# main.net
KiCad netlist of a schematic drawn in Altium Designer
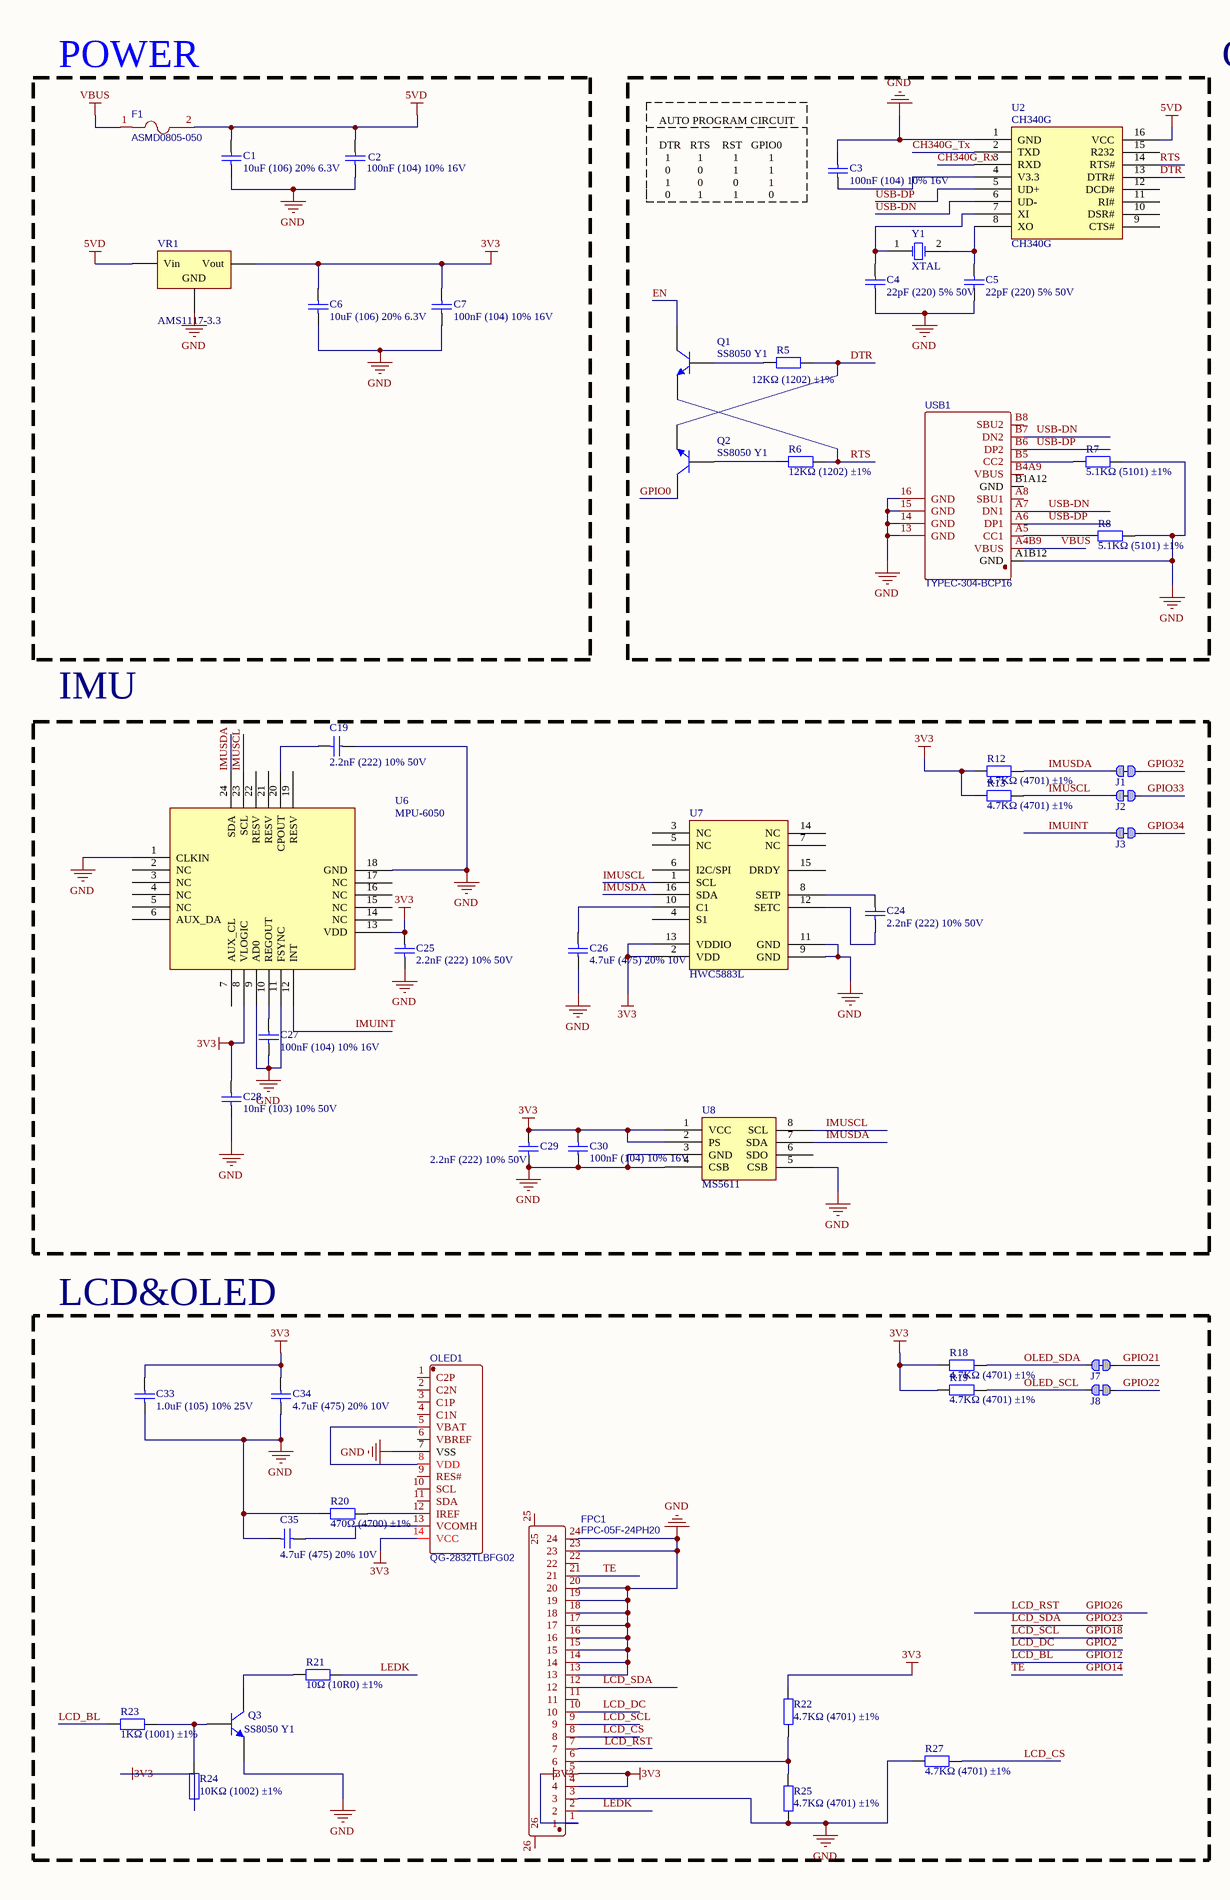
[diagram p0: main.SchDoc, left]
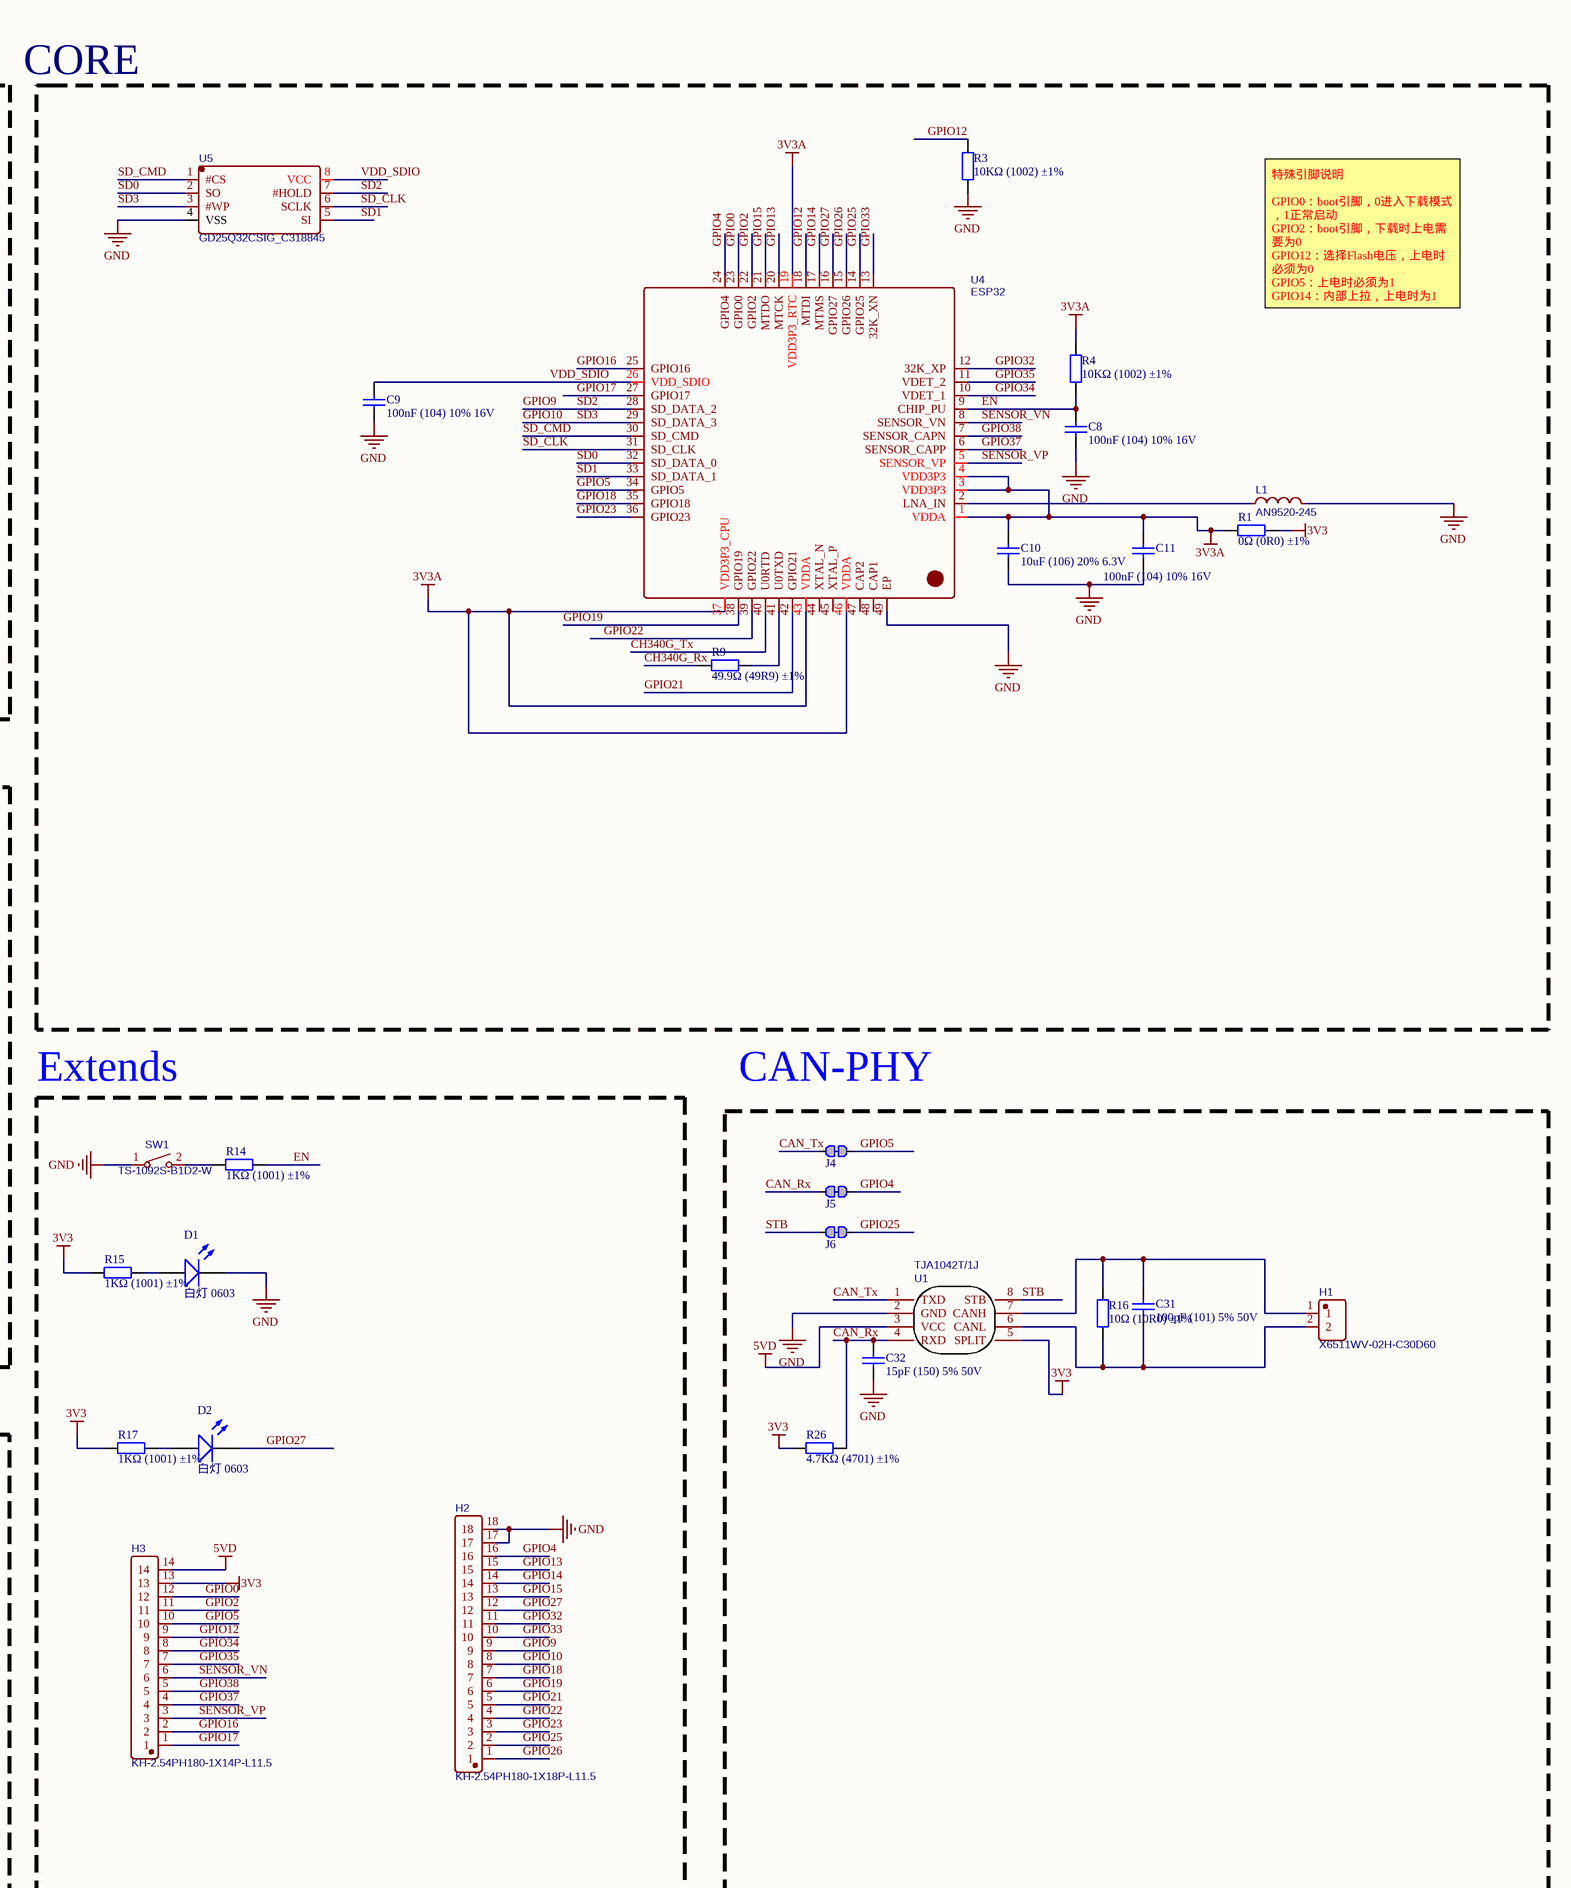
[diagram p1: main.SchDoc, right]

(export (version "E")
  (design (tool "Eeschema 10.0.6"))
  (components
    (comp (ref "C1")
      (value "10uF (106) 20% 6.3V")
      (footprint "0402_C")
      (description "贴片电容")
      (libsource (lib "Cap") (part "0402 10uF (106) 20% 6.3V"))
    )
    (comp (ref "C2")
      (value "100nF (104) 10% 16V")
      (footprint "0402_C")
      (description "贴片电容")
      (libsource (lib "Cap") (part "0402 100nF (104) 10% 16V"))
    )
    (comp (ref "C3")
      (value "100nF (104) 10% 16V")
      (footprint "0402_C")
      (description "贴片电容")
      (libsource (lib "Cap") (part "0402 100nF (104) 10% 16V"))
    )
    (comp (ref "C4")
      (value "22pF (220) 5% 50V")
      (footprint "0402_C")
      (description "贴片电容")
      (libsource (lib "Cap") (part "0402 22pF (220) 5% 50V"))
    )
    (comp (ref "C5")
      (value "22pF (220) 5% 50V")
      (footprint "0402_C")
      (description "贴片电容")
      (libsource (lib "Cap") (part "0402 22pF (220) 5% 50V"))
    )
    (comp (ref "C6")
      (value "10uF (106) 20% 6.3V")
      (footprint "0402_C")
      (description "贴片电容")
      (libsource (lib "Cap") (part "0402 10uF (106) 20% 6.3V"))
    )
    (comp (ref "C7")
      (value "100nF (104) 10% 16V")
      (footprint "0402_C")
      (description "贴片电容")
      (libsource (lib "Cap") (part "0402 100nF (104) 10% 16V"))
    )
    (comp (ref "C8")
      (value "100nF (104) 10% 16V")
      (footprint "0402_C")
      (description "贴片电容")
      (libsource (lib "Cap") (part "0402 100nF (104) 10% 16V"))
    )
    (comp (ref "C9")
      (value "100nF (104) 10% 16V")
      (footprint "0402_C")
      (description "贴片电容")
      (libsource (lib "Cap") (part "0402 100nF (104) 10% 16V"))
    )
    (comp (ref "C10")
      (value "10uF (106) 20% 6.3V")
      (footprint "0402_C")
      (description "贴片电容")
      (libsource (lib "Cap") (part "0402 10uF (106) 20% 6.3V"))
    )
    (comp (ref "C11")
      (value "100nF (104) 10% 16V")
      (footprint "0402_C")
      (description "贴片电容")
      (libsource (lib "Cap") (part "0402 100nF (104) 10% 16V"))
    )
    (comp (ref "C19")
      (value "2.2nF (222) 10% 50V")
      (footprint "0402_C")
      (description "贴片电容")
      (libsource (lib "Cap") (part "0402 2.2nF (222) 10% 50V"))
    )
    (comp (ref "C24")
      (value "2.2nF (222) 10% 50V")
      (footprint "0603_C")
      (description "贴片电容")
      (libsource (lib "Cap") (part "0603 2.2nF (222) 10% 50V"))
    )
    (comp (ref "C25")
      (value "2.2nF (222) 10% 50V")
      (footprint "0402_C")
      (description "贴片电容")
      (libsource (lib "Cap") (part "0402 2.2nF (222) 10% 50V"))
    )
    (comp (ref "C26")
      (value "4.7uF (475) 20% 10V")
      (footprint "0402_C")
      (description "贴片电容")
      (libsource (lib "Cap") (part "0402 4.7uF (475) 20% 10V"))
    )
    (comp (ref "C27")
      (value "100nF (104) 10% 16V")
      (footprint "0402_C")
      (description "贴片电容")
      (libsource (lib "Cap") (part "0402 100nF (104) 10% 16V"))
    )
    (comp (ref "C28")
      (value "10nF (103) 10% 50V")
      (footprint "0402_C")
      (description "贴片电容")
      (libsource (lib "Cap") (part "0402 10nF (103) 10% 50V"))
    )
    (comp (ref "C29")
      (value "2.2nF (222) 10% 50V")
      (footprint "0402_C")
      (description "贴片电容")
      (libsource (lib "Cap") (part "0402 2.2nF (222) 10% 50V"))
    )
    (comp (ref "C30")
      (value "100nF (104) 10% 16V")
      (footprint "0402_C")
      (description "贴片电容")
      (libsource (lib "Cap") (part "0402 100nF (104) 10% 16V"))
    )
    (comp (ref "C31")
      (value "100pF (101) 5% 50V")
      (footprint "0402_C")
      (description "贴片电容")
      (libsource (lib "Cap") (part "0402 100pF (101) 5% 50V"))
    )
    (comp (ref "C32")
      (value "15pF (150) 5% 50V")
      (footprint "0402_C")
      (description "贴片电容")
      (libsource (lib "Cap") (part "0402 15pF (150) 5% 50V"))
    )
    (comp (ref "C33")
      (value "1.0uF (105) 10% 25V")
      (footprint "0402_C")
      (description "贴片电容")
      (libsource (lib "Cap") (part "0402 1.0uF (105) 10% 25V"))
    )
    (comp (ref "C34")
      (value "4.7uF (475) 20% 10V")
      (footprint "0402_C")
      (description "贴片电容")
      (libsource (lib "Cap") (part "0402 4.7uF (475) 20% 10V"))
    )
    (comp (ref "C35")
      (value "4.7uF (475) 20% 10V")
      (footprint "0402_C")
      (description "贴片电容")
      (libsource (lib "Cap") (part "0402 4.7uF (475) 20% 10V"))
    )
    (comp (ref "D1")
      (value "白灯 0603")
      (footprint "0603_LED_S1")
      (description "发光二极管")
      (libsource (lib "Miscellaneous Devices LC") (part "0603 白灯"))
    )
    (comp (ref "D2")
      (value "白灯 0603")
      (footprint "0603_LED_S1")
      (description "发光二极管")
      (libsource (lib "Miscellaneous Devices LC") (part "0603 白灯"))
    )
    (comp (ref "F1")
      (value "ASMD0805-050")
      (footprint "F0805")
      (fields (field (name "BOM_SUPPLIER PART") "C135329"))
      (libsource (lib "mypkg") (part "ASMD0805-050"))
    )
    (comp (ref "FPC1")
      (value "FPC-05F-24PH20")
      (footprint "FPC-SMD_24P-P0.50_FPC-05F-24PH20")
      (description "FPC24脚")
      (fields (field (name "BOM_SUPPLIER PART") "C2856805"))
      (libsource (lib "mysch") (part "FPC-05F-24PH20"))
    )
    (comp (ref "H1")
      (value "X6511WV-02H-C30D60")
      (footprint "HDR-TH_2P-P2.54-V-M")
      (fields (field (name "BOM_SUPPLIER PART") "C706874"))
      (libsource (lib "mysch") (part "HDR-2P"))
    )
    (comp (ref "H2")
      (value "KH-2.54PH180-1X18P-L11.5")
      (footprint "HDR-TH_18P-P2.54-V-M")
      (fields (field (name "BOM_SUPPLIER PART") "C2905492"))
      (libsource (lib "mysch") (part "HDR-18P"))
    )
    (comp (ref "H3")
      (value "KH-2.54PH180-1X14P-L11.5")
      (footprint "HDR-TH_14P-P2.54-V-M")
      (description "排针")
      (fields (field (name "BOM_SUPPLIER PART") "C2905490"))
      (libsource (lib "mysch") (part "HDR-14P"))
    )
    (comp (ref "J1")
      (value "跳线")
      (footprint "RES_0402")
      (description "Resistor")
      (libsource (lib "mysch") (part "跳线"))
    )
    (comp (ref "J2")
      (value "跳线")
      (footprint "RES_0402")
      (description "Resistor")
      (libsource (lib "mysch") (part "跳线"))
    )
    (comp (ref "J3")
      (value "跳线")
      (footprint "RES_0402")
      (description "Resistor")
      (libsource (lib "mysch") (part "跳线"))
    )
    (comp (ref "J4")
      (value "跳线")
      (footprint "RES_0402")
      (description "Resistor")
      (libsource (lib "mysch") (part "跳线"))
    )
    (comp (ref "J5")
      (value "跳线")
      (footprint "RES_0402")
      (description "Resistor")
      (libsource (lib "mysch") (part "跳线"))
    )
    (comp (ref "J6")
      (value "跳线")
      (footprint "RES_0402")
      (description "Resistor")
      (libsource (lib "mysch") (part "跳线"))
    )
    (comp (ref "J7")
      (value "跳线")
      (footprint "RES_0402")
      (description "Resistor")
      (libsource (lib "mysch") (part "跳线"))
    )
    (comp (ref "J8")
      (value "跳线")
      (footprint "RES_0402")
      (description "Resistor")
      (libsource (lib "mysch") (part "跳线"))
    )
    (comp (ref "L1")
      (value "AN9520-245")
      (footprint "ANT-SMD_L9.5-W2.1")
      (description "陶瓷wifi/bt天线")
      (fields (field (name "BOM_SUPPLIER PART") "C99665"))
      (libsource (lib "mypkg") (part "AN9520-245"))
    )
    (comp (ref "OLED1")
      (value "QG-2832TLBFG02")
      (footprint "OLED-SMD_QG-9616TSWCG02")
      (fields (field (name "BOM_SUPPLIER PART") "C91220"))
      (libsource (lib "mysch") (part "OLED"))
    )
    (comp (ref "Q1")
      (value "SS8050 Y1")
      (footprint "SOT-23(SOT-23-3)")
      (description "三极管")
      (libsource (lib "Miscellaneous Devices LC") (part "SOT-23 SS8050 Y1"))
    )
    (comp (ref "Q2")
      (value "SS8050 Y1")
      (footprint "SOT-23(SOT-23-3)")
      (description "三极管")
      (libsource (lib "Miscellaneous Devices LC") (part "SOT-23 SS8050 Y1"))
    )
    (comp (ref "Q3")
      (value "SS8050 Y1")
      (footprint "SOT-23(SOT-23-3)")
      (description "三极管")
      (libsource (lib "Miscellaneous Devices LC") (part "SOT-23 SS8050 Y1"))
    )
    (comp (ref "R1")
      (value "0Ω (0R0) ±1%")
      (footprint "0402_R")
      (description "贴片电阻")
      (libsource (lib "RES") (part "0402 0Ω (0R0) 1%"))
    )
    (comp (ref "R3")
      (value "10KΩ (1002) ±1%")
      (footprint "0402_R")
      (description "贴片电阻")
      (libsource (lib "RES") (part "0402 10KΩ (1002) 1%"))
    )
    (comp (ref "R4")
      (value "10KΩ (1002) ±1%")
      (footprint "0402_R")
      (description "贴片电阻")
      (libsource (lib "RES") (part "0402 10KΩ (1002) 1%"))
    )
    (comp (ref "R5")
      (value "12KΩ (1202) ±1%")
      (footprint "0402_R")
      (description "贴片电阻")
      (libsource (lib "RES") (part "0402 12KΩ (1202) 1%"))
    )
    (comp (ref "R6")
      (value "12KΩ (1202) ±1%")
      (footprint "0402_R")
      (description "贴片电阻")
      (libsource (lib "RES") (part "0402 12KΩ (1202) 1%"))
    )
    (comp (ref "R7")
      (value "5.1KΩ (5101) ±1%")
      (footprint "0402_R")
      (description "贴片电阻")
      (libsource (lib "RES") (part "0402 5.1KΩ (5101) 1%"))
    )
    (comp (ref "R8")
      (value "5.1KΩ (5101) ±1%")
      (footprint "0402_R")
      (description "贴片电阻")
      (libsource (lib "RES") (part "0402 5.1KΩ (5101) 1%"))
    )
    (comp (ref "R9")
      (value "49.9Ω (49R9) ±1%")
      (footprint "0402_R")
      (description "贴片电阻")
      (libsource (lib "RES") (part "0402 49.9Ω (49R9) 1%"))
    )
    (comp (ref "R12")
      (value "4.7KΩ (4701) ±1%")
      (footprint "0402_R")
      (description "贴片电阻")
      (libsource (lib "") (part "0402 4.7KΩ (4701) 1%_1"))
    )
    (comp (ref "R13")
      (value "4.7KΩ (4701) ±1%")
      (footprint "0402_R")
      (description "贴片电阻")
      (libsource (lib "") (part "0402 4.7KΩ (4701) 1%_1"))
    )
    (comp (ref "R14")
      (value "1KΩ (1001) ±1%")
      (footprint "0402_R")
      (description "贴片电阻")
      (libsource (lib "RES") (part "0402 1KΩ (1001) 1%"))
    )
    (comp (ref "R15")
      (value "1KΩ (1001) ±1%")
      (footprint "0402_R")
      (description "贴片电阻")
      (libsource (lib "RES") (part "0402 1KΩ (1001) 1%"))
    )
    (comp (ref "R16")
      (value "10Ω (10R0) ±1%")
      (footprint "0402_R")
      (description "贴片电阻")
      (libsource (lib "") (part "0402 10Ω (10R0) 1%_1"))
    )
    (comp (ref "R17")
      (value "1KΩ (1001) ±1%")
      (footprint "0402_R")
      (description "贴片电阻")
      (libsource (lib "RES") (part "0402 1KΩ (1001) 1%"))
    )
    (comp (ref "R18")
      (value "4.7KΩ (4701) ±1%")
      (footprint "0402_R")
      (description "贴片电阻")
      (libsource (lib "") (part "0402 4.7KΩ (4701) 1%_1"))
    )
    (comp (ref "R19")
      (value "4.7KΩ (4701) ±1%")
      (footprint "0402_R")
      (description "贴片电阻")
      (libsource (lib "") (part "0402 4.7KΩ (4701) 1%_1"))
    )
    (comp (ref "R20")
      (value "470Ω (4700) ±1%")
      (footprint "0402_R")
      (description "贴片电阻")
      (libsource (lib "RES") (part "0402 470Ω (4700) 1%"))
    )
    (comp (ref "R21")
      (value "10Ω (10R0) ±1%")
      (footprint "0402_R")
      (description "贴片电阻")
      (libsource (lib "RES") (part "0402 10Ω (10R0) 1%"))
    )
    (comp (ref "R22")
      (value "4.7KΩ (4701) ±1%")
      (footprint "0402_R")
      (description "贴片电阻")
      (libsource (lib "RES") (part "0402 4.7KΩ (4701) 1%"))
    )
    (comp (ref "R23")
      (value "1KΩ (1001) ±1%")
      (footprint "0402_R")
      (description "贴片电阻")
      (libsource (lib "RES") (part "0402 1KΩ (1001) 1%"))
    )
    (comp (ref "R24")
      (value "10KΩ (1002) ±1%")
      (footprint "0402_R")
      (description "贴片电阻")
      (libsource (lib "RES") (part "0402 10KΩ (1002) 1%"))
    )
    (comp (ref "R25")
      (value "4.7KΩ (4701) ±1%")
      (footprint "0402_R")
      (description "贴片电阻")
      (libsource (lib "RES") (part "0402 4.7KΩ (4701) 1%"))
    )
    (comp (ref "R26")
      (value "4.7KΩ (4701) ±1%")
      (footprint "0402_R")
      (description "贴片电阻")
      (libsource (lib "") (part "0402 4.7KΩ (4701) 1%_1"))
    )
    (comp (ref "R27")
      (value "4.7KΩ (4701) ±1%")
      (footprint "0402_R")
      (description "贴片电阻")
      (libsource (lib "") (part "0402 4.7KΩ (4701) 1%_1"))
    )
    (comp (ref "SW1")
      (value "TS-1092S-B1D2-W")
      (footprint "SW-SMD_L6.1-W3.6-LS7.9")
      (description "触控开关")
      (fields (field (name "BOM_SUPPLIER PART") "C782859"))
      (libsource (lib "mysch") (part "TS-1092S-B1D2-W"))
    )
    (comp (ref "U1")
      (value "TJA1042T/1J")
      (footprint "SOIC-8_L5.0-W4.0-P1.27-LS6.0-BL")
      (description "CAN芯片")
      (fields (field (name "BOM_SUPPLIER PART") "C53670"))
      (libsource (lib "mysch") (part "TJA1042T/1J"))
    )
    (comp (ref "U2")
      (value "CH340G")
      (footprint "SOIC-16_150mil")
      (description "USB")
      (libsource (lib "IC") (part "CH340G_[C14267]"))
    )
    (comp (ref "U4")
      (value "ESP32")
      (footprint "QFN-48-EP3.8")
      (fields (field (name "BOM_SUPPLIER PART") "C80134"))
      (libsource (lib "mypkg") (part "ESP32"))
    )
    (comp (ref "U5")
      (value "GD25Q32CSIG_C318845")
      (footprint "SOIC-8_L5.3-W5.3-P1.27-LS8.0-BL")
      (fields
        (field (name "BOM_SUPPLIER PART") "C318845")
        (field (name "BOM_MANUFACTURER PART") "GD25Q32CSIG")
      )
      (libsource (lib "mysch") (part "GD25Q32CSIG_C318845"))
    )
    (comp (ref "U6")
      (value "MPU-6050")
      (footprint "QFN-24_4x4x05P")
      (description "传感器")
      (libsource (lib "IC") (part "MPU-6050_[C24112]"))
    )
    (comp (ref "U7")
      (value "HWC5883L")
      (footprint "LPCC-16_L3.0-W3.0-P0.50-BL")
      (libsource (lib "mypkg") (part "HMC5883L"))
    )
    (comp (ref "U8") (value "MS5611") (footprint "MS5611") (libsource (lib "mysch") (part "MS5611")))
    (comp (ref "USB1")
      (value "TYPEC-304-BCP16")
      (footprint "USB-C-SMD_TYPEC-304-BCP16")
      (fields (field (name "BOM_SUPPLIER PART") "C720629"))
      (libsource (lib "mysch") (part "TYPEC-304-BCP16"))
    )
    (comp (ref "VR1")
      (value "AMS1117-3.3")
      (footprint "SOT-223")
      (description "低压差线性稳压(LDO)")
      (libsource (lib "LDO") (part "SOT-223 AMS1117-3.3"))
    )
    (comp (ref "Y1")
      (value "XTAL")
      (footprint "XTAL_socket")
      (description "Crystal Oscillator")
      (libsource (lib "mysch") (part "XTAL"))
    )
  )
  (nets
    (net (code "1") (name "/CAN_Rx") (class "Default")
      (node (ref "C32") (pin "2") (pinfunction "2_2") (pintype "passive"))
      (node (ref "J5") (pin "1") (pinfunction "1_1") (pintype "passive"))
      (node (ref "R26") (pin "2") (pinfunction "2_2") (pintype "passive"))
      (node (ref "U1") (pin "4") (pinfunction "RXD_4") (pintype "passive"))
    )
    (net (code "2") (name "/CAN_Tx") (class "Default")
      (node (ref "J4") (pin "1") (pinfunction "1_1") (pintype "passive"))
      (node (ref "U1") (pin "1") (pinfunction "TXD_1") (pintype "passive"))
    )
    (net (code "3") (name "/CH340G_Rx") (class "Default")
      (node (ref "R9") (pin "1") (pinfunction "1_1") (pintype "passive"))
      (node (ref "U2") (pin "3") (pinfunction "RXD_3") (pintype "passive"))
    )
    (net (code "4") (name "/CH340G_Tx") (class "Default")
      (node (ref "U2") (pin "2") (pinfunction "TXD_2") (pintype "passive"))
      (node (ref "U4") (pin "40") (pinfunction "U0RTD_40") (pintype "passive"))
    )
    (net (code "5") (name "/DTR") (class "Default")
      (node (ref "Q2") (pin "2") (pinfunction "E_2") (pintype "passive"))
      (node (ref "R5") (pin "2") (pinfunction "2_2") (pintype "passive"))
      (node (ref "U2") (pin "13") (pinfunction "DTR#_13") (pintype "passive"))
    )
    (net (code "6") (name "/EN") (class "Default")
      (node (ref "C8") (pin "2") (pinfunction "2_2") (pintype "passive"))
      (node (ref "Q1") (pin "3") (pinfunction "C_3") (pintype "passive"))
      (node (ref "R14") (pin "2") (pinfunction "2_2") (pintype "passive"))
      (node (ref "R4") (pin "1") (pinfunction "1_1") (pintype "passive"))
      (node (ref "U4") (pin "9") (pinfunction "CHIP_PU_9") (pintype "passive"))
    )
    (net (code "7") (name "/GPIO0") (class "Default")
      (node (ref "H3") (pin "12") (pinfunction "12_12") (pintype "passive"))
      (node (ref "Q2") (pin "3") (pinfunction "C_3") (pintype "passive"))
      (node (ref "U4") (pin "23") (pinfunction "GPIO0_23") (pintype "passive"))
    )
    (net (code "8") (name "/GPIO2") (class "Default")
      (node (ref "FPC1") (pin "10") (pinfunction "10_10") (pintype "passive"))
      (node (ref "H3") (pin "11") (pinfunction "11_11") (pintype "passive"))
      (node (ref "U4") (pin "22") (pinfunction "GPIO2_22") (pintype "passive"))
    )
    (net (code "9") (name "/GPIO4") (class "Default")
      (node (ref "H2") (pin "16") (pinfunction "16_16") (pintype "passive"))
      (node (ref "J5") (pin "2") (pinfunction "2_2") (pintype "passive"))
      (node (ref "U4") (pin "24") (pinfunction "GPIO4_24") (pintype "passive"))
    )
    (net (code "10") (name "/GPIO5") (class "Default")
      (node (ref "H3") (pin "10") (pinfunction "10_10") (pintype "passive"))
      (node (ref "J4") (pin "2") (pinfunction "2_2") (pintype "passive"))
      (node (ref "U4") (pin "34") (pinfunction "GPIO5_34") (pintype "passive"))
    )
    (net (code "11") (name "/GPIO9") (class "Default")
      (node (ref "H2") (pin "9") (pinfunction "9_9") (pintype "passive"))
      (node (ref "U4") (pin "28") (pinfunction "SD_DATA_2_28") (pintype "passive"))
      (node (ref "U5") (pin "7") (pinfunction "#HOLD_7") (pintype "passive"))
    )
    (net (code "12") (name "/GPIO10") (class "Default")
      (node (ref "H2") (pin "8") (pinfunction "8_8") (pintype "passive"))
      (node (ref "U4") (pin "29") (pinfunction "SD_DATA_3_29") (pintype "passive"))
      (node (ref "U5") (pin "3") (pinfunction "#WP_3") (pintype "passive"))
    )
    (net (code "13") (name "/GPIO12") (class "Default")
      (node (ref "H3") (pin "9") (pinfunction "9_9") (pintype "passive"))
      (node (ref "R23") (pin "1") (pinfunction "1_1") (pintype "passive"))
      (node (ref "R3") (pin "2") (pinfunction "2_2") (pintype "passive"))
      (node (ref "U4") (pin "18") (pinfunction "MTDI_18") (pintype "passive"))
    )
    (net (code "14") (name "/GPIO13") (class "Default")
      (node (ref "H2") (pin "15") (pinfunction "15_15") (pintype "passive"))
      (node (ref "U4") (pin "20") (pinfunction "MTCK_20") (pintype "passive"))
    )
    (net (code "15") (name "/GPIO14") (class "Default")
      (node (ref "FPC1") (pin "21") (pinfunction "21_21") (pintype "passive"))
      (node (ref "H2") (pin "14") (pinfunction "14_14") (pintype "passive"))
      (node (ref "U4") (pin "17") (pinfunction "MTMS_17") (pintype "passive"))
    )
    (net (code "16") (name "/GPIO15") (class "Default")
      (node (ref "H2") (pin "13") (pinfunction "13_13") (pintype "passive"))
      (node (ref "U4") (pin "21") (pinfunction "MTDO_21") (pintype "passive"))
    )
    (net (code "17") (name "/GPIO16") (class "Default")
      (node (ref "H3") (pin "2") (pinfunction "2_2") (pintype "passive"))
      (node (ref "U4") (pin "25") (pinfunction "GPIO16_25") (pintype "passive"))
    )
    (net (code "18") (name "/GPIO17") (class "Default")
      (node (ref "H3") (pin "1") (pinfunction "1_1") (pintype "passive"))
      (node (ref "U4") (pin "27") (pinfunction "GPIO17_27") (pintype "passive"))
    )
    (net (code "19") (name "/GPIO18") (class "Default")
      (node (ref "FPC1") (pin "9") (pinfunction "9_9") (pintype "passive"))
      (node (ref "H2") (pin "7") (pinfunction "7_7") (pintype "passive"))
      (node (ref "U4") (pin "35") (pinfunction "GPIO18_35") (pintype "passive"))
    )
    (net (code "20") (name "/GPIO19") (class "Default")
      (node (ref "H2") (pin "6") (pinfunction "6_6") (pintype "passive"))
      (node (ref "U4") (pin "38") (pinfunction "GPIO19_38") (pintype "passive"))
    )
    (net (code "21") (name "/GPIO21") (class "Default")
      (node (ref "H2") (pin "5") (pinfunction "5_5") (pintype "passive"))
      (node (ref "J7") (pin "2") (pinfunction "2_2") (pintype "passive"))
      (node (ref "U4") (pin "42") (pinfunction "GPIO21_42") (pintype "passive"))
    )
    (net (code "22") (name "/GPIO22") (class "Default")
      (node (ref "H2") (pin "4") (pinfunction "4_4") (pintype "passive"))
      (node (ref "J8") (pin "2") (pinfunction "2_2") (pintype "passive"))
      (node (ref "U4") (pin "39") (pinfunction "GPIO22_39") (pintype "passive"))
    )
    (net (code "23") (name "/GPIO23") (class "Default")
      (node (ref "FPC1") (pin "12") (pinfunction "12_12") (pintype "passive"))
      (node (ref "H2") (pin "3") (pinfunction "3_3") (pintype "passive"))
      (node (ref "U4") (pin "36") (pinfunction "GPIO23_36") (pintype "passive"))
    )
    (net (code "24") (name "/GPIO25") (class "Default")
      (node (ref "H2") (pin "2") (pinfunction "2_2") (pintype "passive"))
      (node (ref "J6") (pin "2") (pinfunction "2_2") (pintype "passive"))
      (node (ref "U4") (pin "14") (pinfunction "GPIO25_14") (pintype "passive"))
    )
    (net (code "25") (name "/GPIO26") (class "Default")
      (node (ref "FPC1") (pin "7") (pinfunction "7_7") (pintype "passive"))
      (node (ref "H2") (pin "1") (pinfunction "1_1") (pintype "passive"))
      (node (ref "U4") (pin "15") (pinfunction "GPIO26_15") (pintype "passive"))
    )
    (net (code "26") (name "/GPIO27") (class "Default")
      (node (ref "D2") (pin "K") (pinfunction "K_K") (pintype "passive"))
      (node (ref "H2") (pin "12") (pinfunction "12_12") (pintype "passive"))
      (node (ref "U4") (pin "16") (pinfunction "GPIO27_16") (pintype "passive"))
    )
    (net (code "27") (name "/GPIO32") (class "Default")
      (node (ref "H2") (pin "11") (pinfunction "11_11") (pintype "passive"))
      (node (ref "J1") (pin "2") (pinfunction "2_2") (pintype "passive"))
      (node (ref "U4") (pin "12") (pinfunction "32K_XP_12") (pintype "passive"))
    )
    (net (code "28") (name "/GPIO33") (class "Default")
      (node (ref "H2") (pin "10") (pinfunction "10_10") (pintype "passive"))
      (node (ref "J2") (pin "2") (pinfunction "2_2") (pintype "passive"))
      (node (ref "U4") (pin "13") (pinfunction "32K_XN_13") (pintype "passive"))
    )
    (net (code "29") (name "/GPIO34") (class "Default")
      (node (ref "H3") (pin "8") (pinfunction "8_8") (pintype "passive"))
      (node (ref "J3") (pin "2") (pinfunction "2_2") (pintype "passive"))
      (node (ref "U4") (pin "10") (pinfunction "VDET_1_10") (pintype "passive"))
    )
    (net (code "30") (name "/GPIO35") (class "Default")
      (node (ref "H3") (pin "7") (pinfunction "7_7") (pintype "passive"))
      (node (ref "U4") (pin "11") (pinfunction "VDET_2_11") (pintype "passive"))
    )
    (net (code "31") (name "/GPIO37") (class "Default")
      (node (ref "H3") (pin "4") (pinfunction "4_4") (pintype "passive"))
      (node (ref "U4") (pin "6") (pinfunction "SENSOR_CAPP_6") (pintype "passive"))
    )
    (net (code "32") (name "/GPIO38") (class "Default")
      (node (ref "H3") (pin "5") (pinfunction "5_5") (pintype "passive"))
      (node (ref "U4") (pin "7") (pinfunction "SENSOR_CAPN_7") (pintype "passive"))
    )
    (net (code "33") (name "/IMUINT") (class "Default")
      (node (ref "J3") (pin "1") (pinfunction "1_1") (pintype "passive"))
      (node (ref "U6") (pin "12") (pinfunction "INT_12") (pintype "passive"))
    )
    (net (code "34") (name "/IMUSCL") (class "Default")
      (node (ref "J2") (pin "1") (pinfunction "1_1") (pintype "passive"))
      (node (ref "R13") (pin "2") (pinfunction "2_2") (pintype "passive"))
      (node (ref "U6") (pin "23") (pinfunction "SCL_23") (pintype "passive"))
      (node (ref "U7") (pin "1") (pinfunction "SCL_1") (pintype "passive"))
      (node (ref "U8") (pin "8") (pinfunction "SCL_8") (pintype "passive"))
    )
    (net (code "35") (name "/IMUSDA") (class "Default")
      (node (ref "J1") (pin "1") (pinfunction "1_1") (pintype "passive"))
      (node (ref "R12") (pin "2") (pinfunction "2_2") (pintype "passive"))
      (node (ref "U6") (pin "24") (pinfunction "SDA_24") (pintype "passive"))
      (node (ref "U7") (pin "16") (pinfunction "SDA_16") (pintype "passive"))
      (node (ref "U8") (pin "7") (pinfunction "SDA_7") (pintype "passive"))
    )
    (net (code "36") (name "/LCD_CS") (class "Default")
      (node (ref "FPC1") (pin "8") (pinfunction "8_8") (pintype "passive"))
      (node (ref "R27") (pin "2") (pinfunction "2_2") (pintype "passive"))
    )
    (net (code "37") (name "/LEDK") (class "Default")
      (node (ref "FPC1") (pin "2") (pinfunction "2_2") (pintype "passive"))
      (node (ref "R21") (pin "2") (pinfunction "2_2") (pintype "passive"))
    )
    (net (code "38") (name "/OLED_SCL") (class "Default")
      (node (ref "J8") (pin "1") (pinfunction "1_1") (pintype "passive"))
      (node (ref "R19") (pin "2") (pinfunction "2_2") (pintype "passive"))
    )
    (net (code "39") (name "/OLED_SDA") (class "Default")
      (node (ref "J7") (pin "1") (pinfunction "1_1") (pintype "passive"))
      (node (ref "R18") (pin "2") (pinfunction "2_2") (pintype "passive"))
    )
    (net (code "40") (name "/RTS") (class "Default")
      (node (ref "Q1") (pin "2") (pinfunction "E_2") (pintype "passive"))
      (node (ref "R6") (pin "2") (pinfunction "2_2") (pintype "passive"))
      (node (ref "U2") (pin "14") (pinfunction "RTS#_14") (pintype "passive"))
    )
    (net (code "41") (name "/SD0") (class "Default")
      (node (ref "U4") (pin "32") (pinfunction "SD_DATA_0_32") (pintype "passive"))
      (node (ref "U5") (pin "2") (pinfunction "SO_2") (pintype "passive"))
    )
    (net (code "42") (name "/SD1") (class "Default")
      (node (ref "U4") (pin "33") (pinfunction "SD_DATA_1_33") (pintype "passive"))
      (node (ref "U5") (pin "5") (pinfunction "SI_5") (pintype "passive"))
    )
    (net (code "43") (name "/SD_CLK") (class "Default")
      (node (ref "U4") (pin "31") (pinfunction "SD_CLK_31") (pintype "passive"))
      (node (ref "U5") (pin "6") (pinfunction "SCLK_6") (pintype "passive"))
    )
    (net (code "44") (name "/SD_CMD") (class "Default")
      (node (ref "U4") (pin "30") (pinfunction "SD_CMD_30") (pintype "passive"))
      (node (ref "U5") (pin "1") (pinfunction "#CS_1") (pintype "passive"))
    )
    (net (code "45") (name "/SENSOR_VN") (class "Default")
      (node (ref "H3") (pin "6") (pinfunction "6_6") (pintype "passive"))
      (node (ref "U4") (pin "8") (pinfunction "SENSOR_VN_8") (pintype "passive"))
    )
    (net (code "46") (name "/SENSOR_VP") (class "Default")
      (node (ref "H3") (pin "3") (pinfunction "3_3") (pintype "passive"))
      (node (ref "U4") (pin "5") (pinfunction "SENSOR_VP_5") (pintype "passive"))
    )
    (net (code "47") (name "/STB") (class "Default")
      (node (ref "J6") (pin "1") (pinfunction "1_1") (pintype "passive"))
      (node (ref "U1") (pin "8") (pinfunction "STB_8") (pintype "passive"))
    )
    (net (code "48") (name "/USB-DN") (class "Default")
      (node (ref "U2") (pin "6") (pinfunction "UD-_6") (pintype "passive"))
      (node (ref "USB1") (pin "A7") (pinfunction "DN1_A7") (pintype "passive"))
      (node (ref "USB1") (pin "B7") (pinfunction "DN2_B7") (pintype "passive"))
    )
    (net (code "49") (name "/USB-DP") (class "Default")
      (node (ref "U2") (pin "5") (pinfunction "UD+_5") (pintype "passive"))
      (node (ref "USB1") (pin "A6") (pinfunction "DP1_A6") (pintype "passive"))
      (node (ref "USB1") (pin "B6") (pinfunction "DP2_B6") (pintype "passive"))
    )
    (net (code "50") (name "/VDD_SDIO") (class "Default")
      (node (ref "C9") (pin "2") (pinfunction "2_2") (pintype "passive"))
      (node (ref "U4") (pin "26") (pinfunction "VDD_SDIO_26") (pintype "passive"))
      (node (ref "U5") (pin "8") (pinfunction "VCC_8") (pintype "passive"))
    )
    (net (code "51") (name "3V3") (class "Default")
      (node (ref "C25") (pin "2") (pinfunction "2_2") (pintype "passive"))
      (node (ref "C28") (pin "2") (pinfunction "2_2") (pintype "passive"))
      (node (ref "C29") (pin "2") (pinfunction "2_2") (pintype "passive"))
      (node (ref "C30") (pin "2") (pinfunction "2_2") (pintype "passive"))
      (node (ref "C33") (pin "2") (pinfunction "2_2") (pintype "passive"))
      (node (ref "C34") (pin "2") (pinfunction "2_2") (pintype "passive"))
      (node (ref "C6") (pin "2") (pinfunction "2_2") (pintype "passive"))
      (node (ref "C7") (pin "2") (pinfunction "2_2") (pintype "passive"))
      (node (ref "FPC1") (pin "1") (pinfunction "1_1") (pintype "passive"))
      (node (ref "FPC1") (pin "4") (pinfunction "4_4") (pintype "passive"))
      (node (ref "FPC1") (pin "5") (pinfunction "5_5") (pintype "passive"))
      (node (ref "H3") (pin "13") (pinfunction "13_13") (pintype "passive"))
      (node (ref "OLED1") (pin "14") (pinfunction "VCC_14") (pintype "passive"))
      (node (ref "R1") (pin "2") (pinfunction "2_2") (pintype "passive"))
      (node (ref "R12") (pin "1") (pinfunction "1_1") (pintype "passive"))
      (node (ref "R13") (pin "1") (pinfunction "1_1") (pintype "passive"))
      (node (ref "R15") (pin "1") (pinfunction "1_1") (pintype "passive"))
      (node (ref "R17") (pin "1") (pinfunction "1_1") (pintype "passive"))
      (node (ref "R18") (pin "1") (pinfunction "1_1") (pintype "passive"))
      (node (ref "R19") (pin "1") (pinfunction "1_1") (pintype "passive"))
      (node (ref "R22") (pin "2") (pinfunction "2_2") (pintype "passive"))
      (node (ref "R24") (pin "1") (pinfunction "1_1") (pintype "passive"))
      (node (ref "R26") (pin "1") (pinfunction "1_1") (pintype "passive"))
      (node (ref "U1") (pin "5") (pinfunction "SPLIT_5") (pintype "passive"))
      (node (ref "U6") (pin "13") (pinfunction "VDD_13") (pintype "passive"))
      (node (ref "U6") (pin "8") (pinfunction "VLOGIC_8") (pintype "passive"))
      (node (ref "U7") (pin "13") (pinfunction "VDDIO_13") (pintype "passive"))
      (node (ref "U7") (pin "2") (pinfunction "VDD_2") (pintype "passive"))
      (node (ref "U8") (pin "1") (pinfunction "VCC_1") (pintype "passive"))
      (node (ref "U8") (pin "2") (pinfunction "PS_2") (pintype "passive"))
      (node (ref "VR1") (pin "2") (pinfunction "Vout_2") (pintype "passive"))
    )
    (net (code "52") (name "3V3A") (class "Default")
      (node (ref "C10") (pin "2") (pinfunction "2_2") (pintype "passive"))
      (node (ref "C11") (pin "2") (pinfunction "2_2") (pintype "passive"))
      (node (ref "R1") (pin "1") (pinfunction "1_1") (pintype "passive"))
      (node (ref "R4") (pin "2") (pinfunction "2_2") (pintype "passive"))
      (node (ref "U4") (pin "1") (pinfunction "VDDA_1") (pintype "passive"))
      (node (ref "U4") (pin "19") (pinfunction "VDD3P3_RTC_19") (pintype "passive"))
      (node (ref "U4") (pin "3") (pinfunction "VDD3P3_3") (pintype "passive"))
      (node (ref "U4") (pin "37") (pinfunction "VDD3P3_CPU_37") (pintype "passive"))
      (node (ref "U4") (pin "4") (pinfunction "VDD3P3_4") (pintype "passive"))
      (node (ref "U4") (pin "43") (pinfunction "VDDA_43") (pintype "passive"))
      (node (ref "U4") (pin "46") (pinfunction "VDDA_46") (pintype "passive"))
    )
    (net (code "53") (name "5VD") (class "Default")
      (node (ref "C1") (pin "2") (pinfunction "2_2") (pintype "passive"))
      (node (ref "C2") (pin "2") (pinfunction "2_2") (pintype "passive"))
      (node (ref "F1") (pin "2") (pinfunction "2_2") (pintype "passive"))
      (node (ref "H3") (pin "14") (pinfunction "14_14") (pintype "passive"))
      (node (ref "U1") (pin "3") (pinfunction "VCC_3") (pintype "passive"))
      (node (ref "U2") (pin "16") (pinfunction "VCC_16") (pintype "passive"))
      (node (ref "VR1") (pin "3") (pinfunction "Vin_3") (pintype "passive"))
    )
    (net (code "54") (name "GND") (class "Default")
      (node (ref "C1") (pin "1") (pinfunction "1_1") (pintype "passive"))
      (node (ref "C10") (pin "1") (pinfunction "1_1") (pintype "passive"))
      (node (ref "C11") (pin "1") (pinfunction "1_1") (pintype "passive"))
      (node (ref "C19") (pin "2") (pinfunction "2_2") (pintype "passive"))
      (node (ref "C2") (pin "1") (pinfunction "1_1") (pintype "passive"))
      (node (ref "C25") (pin "1") (pinfunction "1_1") (pintype "passive"))
      (node (ref "C26") (pin "1") (pinfunction "1_1") (pintype "passive"))
      (node (ref "C27") (pin "1") (pinfunction "1_1") (pintype "passive"))
      (node (ref "C28") (pin "1") (pinfunction "1_1") (pintype "passive"))
      (node (ref "C29") (pin "1") (pinfunction "1_1") (pintype "passive"))
      (node (ref "C3") (pin "2") (pinfunction "2_2") (pintype "passive"))
      (node (ref "C30") (pin "1") (pinfunction "1_1") (pintype "passive"))
      (node (ref "C32") (pin "1") (pinfunction "1_1") (pintype "passive"))
      (node (ref "C33") (pin "1") (pinfunction "1_1") (pintype "passive"))
      (node (ref "C34") (pin "1") (pinfunction "1_1") (pintype "passive"))
      (node (ref "C35") (pin "1") (pinfunction "1_1") (pintype "passive"))
      (node (ref "C4") (pin "1") (pinfunction "1_1") (pintype "passive"))
      (node (ref "C5") (pin "1") (pinfunction "1_1") (pintype "passive"))
      (node (ref "C6") (pin "1") (pinfunction "1_1") (pintype "passive"))
      (node (ref "C7") (pin "1") (pinfunction "1_1") (pintype "passive"))
      (node (ref "C8") (pin "1") (pinfunction "1_1") (pintype "passive"))
      (node (ref "C9") (pin "1") (pinfunction "1_1") (pintype "passive"))
      (node (ref "D1") (pin "K") (pinfunction "K_K") (pintype "passive"))
      (node (ref "FPC1") (pin "13") (pinfunction "13_13") (pintype "passive"))
      (node (ref "FPC1") (pin "14") (pinfunction "14_14") (pintype "passive"))
      (node (ref "FPC1") (pin "15") (pinfunction "15_15") (pintype "passive"))
      (node (ref "FPC1") (pin "16") (pinfunction "16_16") (pintype "passive"))
      (node (ref "FPC1") (pin "17") (pinfunction "17_17") (pintype "passive"))
      (node (ref "FPC1") (pin "18") (pinfunction "18_18") (pintype "passive"))
      (node (ref "FPC1") (pin "19") (pinfunction "19_19") (pintype "passive"))
      (node (ref "FPC1") (pin "20") (pinfunction "20_20") (pintype "passive"))
      (node (ref "FPC1") (pin "23") (pinfunction "23_23") (pintype "passive"))
      (node (ref "FPC1") (pin "24") (pinfunction "24_24") (pintype "passive"))
      (node (ref "FPC1") (pin "3") (pinfunction "3_3") (pintype "passive"))
      (node (ref "H2") (pin "17") (pinfunction "17_17") (pintype "passive"))
      (node (ref "H2") (pin "18") (pinfunction "18_18") (pintype "passive"))
      (node (ref "L1") (pin "2") (pinfunction "2_2") (pintype "passive"))
      (node (ref "OLED1") (pin "7") (pinfunction "VSS_7") (pintype "passive"))
      (node (ref "Q3") (pin "2") (pinfunction "E_2") (pintype "passive"))
      (node (ref "R20") (pin "1") (pinfunction "1_1") (pintype "passive"))
      (node (ref "R25") (pin "1") (pinfunction "1_1") (pintype "passive"))
      (node (ref "R27") (pin "1") (pinfunction "1_1") (pintype "passive"))
      (node (ref "R3") (pin "1") (pinfunction "1_1") (pintype "passive"))
      (node (ref "R7") (pin "2") (pinfunction "2_2") (pintype "passive"))
      (node (ref "R8") (pin "2") (pinfunction "2_2") (pintype "passive"))
      (node (ref "SW1") (pin "1") (pinfunction "1_1") (pintype "passive"))
      (node (ref "U1") (pin "2") (pinfunction "GND_2") (pintype "passive"))
      (node (ref "U2") (pin "1") (pinfunction "GND_1") (pintype "passive"))
      (node (ref "U4") (pin "49") (pinfunction "EP_49") (pintype "passive"))
      (node (ref "U5") (pin "4") (pinfunction "VSS_4") (pintype "passive"))
      (node (ref "U6") (pin "1") (pinfunction "CLKIN_1") (pintype "passive"))
      (node (ref "U6") (pin "11") (pinfunction "FSYNC_11") (pintype "passive"))
      (node (ref "U6") (pin "18") (pinfunction "GND_18") (pintype "passive"))
      (node (ref "U6") (pin "9") (pinfunction "AD0_9") (pintype "passive"))
      (node (ref "U7") (pin "11") (pinfunction "GND_11") (pintype "passive"))
      (node (ref "U7") (pin "9") (pinfunction "GND_9") (pintype "passive"))
      (node (ref "U8") (pin "3") (pinfunction "GND_3") (pintype "passive"))
      (node (ref "U8") (pin "4") (pinfunction "CSB_4") (pintype "passive"))
      (node (ref "U8") (pin "5") (pinfunction "CSB_5") (pintype "passive"))
      (node (ref "USB1") (pin "13") (pinfunction "GND_13") (pintype "passive"))
      (node (ref "USB1") (pin "14") (pinfunction "GND_14") (pintype "passive"))
      (node (ref "USB1") (pin "15") (pinfunction "GND_15") (pintype "passive"))
      (node (ref "USB1") (pin "16") (pinfunction "GND_16") (pintype "passive"))
      (node (ref "USB1") (pin "A1B12") (pinfunction "GND_A1B12") (pintype "passive"))
      (node (ref "VR1") (pin "1") (pinfunction "GND_1") (pintype "passive"))
    )
    (net (code "55") (name "Net-(D1-PadA)") (class "Default")
      (node (ref "D1") (pin "A") (pinfunction "A_A") (pintype "passive"))
      (node (ref "R15") (pin "2") (pinfunction "2_2") (pintype "passive"))
    )
    (net (code "56") (name "Net-(D2-PadA)") (class "Default")
      (node (ref "D2") (pin "A") (pinfunction "A_A") (pintype "passive"))
      (node (ref "R17") (pin "2") (pinfunction "2_2") (pintype "passive"))
    )
    (net (code "57") (name "Net-(FPC1-Pad6)") (class "Default")
      (node (ref "FPC1") (pin "6") (pinfunction "6_6") (pintype "passive"))
      (node (ref "R22") (pin "1") (pinfunction "1_1") (pintype "passive"))
      (node (ref "R25") (pin "2") (pinfunction "2_2") (pintype "passive"))
    )
    (net (code "58") (name "Net-(OLED1-IREF)") (class "Default")
      (node (ref "OLED1") (pin "12") (pinfunction "IREF_12") (pintype "passive"))
      (node (ref "R20") (pin "2") (pinfunction "2_2") (pintype "passive"))
    )
    (net (code "59") (name "Net-(OLED1-VBAT)") (class "Default")
      (node (ref "OLED1") (pin "5") (pinfunction "VBAT_5") (pintype "passive"))
      (node (ref "OLED1") (pin "8") (pinfunction "VDD_8") (pintype "passive"))
    )
    (net (code "60") (name "Net-(OLED1-VCOMH)") (class "Default")
      (node (ref "C35") (pin "2") (pinfunction "2_2") (pintype "passive"))
      (node (ref "OLED1") (pin "13") (pinfunction "VCOMH_13") (pintype "passive"))
    )
    (net (code "61") (name "Net-(Q1-B)") (class "Default")
      (node (ref "Q1") (pin "1") (pinfunction "B_1") (pintype "passive"))
      (node (ref "R5") (pin "1") (pinfunction "1_1") (pintype "passive"))
    )
    (net (code "62") (name "Net-(Q2-B)") (class "Default")
      (node (ref "Q2") (pin "1") (pinfunction "B_1") (pintype "passive"))
      (node (ref "R6") (pin "1") (pinfunction "1_1") (pintype "passive"))
    )
    (net (code "63") (name "Net-(Q3-B)") (class "Default")
      (node (ref "Q3") (pin "1") (pinfunction "B_1") (pintype "passive"))
      (node (ref "R23") (pin "2") (pinfunction "2_2") (pintype "passive"))
      (node (ref "R24") (pin "2") (pinfunction "2_2") (pintype "passive"))
    )
    (net (code "64") (name "Net-(Q3-C)") (class "Default")
      (node (ref "Q3") (pin "3") (pinfunction "C_3") (pintype "passive"))
      (node (ref "R21") (pin "1") (pinfunction "1_1") (pintype "passive"))
    )
    (net (code "65") (name "Net-(R14-Pad1)") (class "Default")
      (node (ref "R14") (pin "1") (pinfunction "1_1") (pintype "passive"))
      (node (ref "SW1") (pin "2") (pinfunction "2_2") (pintype "passive"))
    )
    (net (code "66") (name "Net-(U1-CANH)") (class "Default")
      (node (ref "C31") (pin "2") (pinfunction "2_2") (pintype "passive"))
      (node (ref "H1") (pin "1") (pinfunction "1_1") (pintype "passive"))
      (node (ref "R16") (pin "2") (pinfunction "2_2") (pintype "passive"))
      (node (ref "U1") (pin "7") (pinfunction "CANH_7") (pintype "passive"))
    )
    (net (code "67") (name "Net-(U1-CANL)") (class "Default")
      (node (ref "C31") (pin "1") (pinfunction "1_1") (pintype "passive"))
      (node (ref "H1") (pin "2") (pinfunction "2_2") (pintype "passive"))
      (node (ref "R16") (pin "1") (pinfunction "1_1") (pintype "passive"))
      (node (ref "U1") (pin "6") (pinfunction "CANL_6") (pintype "passive"))
    )
    (net (code "68") (name "Net-(U2-V3.3)") (class "Default")
      (node (ref "C3") (pin "1") (pinfunction "1_1") (pintype "passive"))
      (node (ref "U2") (pin "4") (pinfunction "V3.3_4") (pintype "passive"))
    )
    (net (code "69") (name "Net-(U2-XI)") (class "Default")
      (node (ref "C4") (pin "2") (pinfunction "2_2") (pintype "passive"))
      (node (ref "U2") (pin "7") (pinfunction "XI_7") (pintype "passive"))
      (node (ref "Y1") (pin "1") (pinfunction "OSC1_1") (pintype "passive"))
    )
    (net (code "70") (name "Net-(U2-XO)") (class "Default")
      (node (ref "C5") (pin "2") (pinfunction "2_2") (pintype "passive"))
      (node (ref "U2") (pin "8") (pinfunction "XO_8") (pintype "passive"))
      (node (ref "Y1") (pin "2") (pinfunction "OSC2_2") (pintype "passive"))
    )
    (net (code "71") (name "Net-(U4-LNA_IN)") (class "Default")
      (node (ref "L1") (pin "1") (pinfunction "1_1") (pintype "passive"))
      (node (ref "U4") (pin "2") (pinfunction "LNA_IN_2") (pintype "passive"))
    )
    (net (code "72") (name "Net-(U4-U0TXD)") (class "Default")
      (node (ref "R9") (pin "2") (pinfunction "2_2") (pintype "passive"))
      (node (ref "U4") (pin "41") (pinfunction "U0TXD_41") (pintype "passive"))
    )
    (net (code "73") (name "Net-(U6-CPOUT)") (class "Default")
      (node (ref "C19") (pin "1") (pinfunction "1_1") (pintype "passive"))
      (node (ref "U6") (pin "20") (pinfunction "CPOUT_20") (pintype "passive"))
    )
    (net (code "74") (name "Net-(U6-REGOUT)") (class "Default")
      (node (ref "C27") (pin "2") (pinfunction "2_2") (pintype "passive"))
      (node (ref "U6") (pin "10") (pinfunction "REGOUT_10") (pintype "passive"))
    )
    (net (code "75") (name "Net-(U7-C1)") (class "Default")
      (node (ref "C26") (pin "2") (pinfunction "2_2") (pintype "passive"))
      (node (ref "U7") (pin "10") (pinfunction "C1_10") (pintype "passive"))
    )
    (net (code "76") (name "Net-(U7-SETC)") (class "Default")
      (node (ref "C24") (pin "1") (pinfunction "1_1") (pintype "passive"))
      (node (ref "U7") (pin "12") (pinfunction "SETC_12") (pintype "passive"))
    )
    (net (code "77") (name "Net-(U7-SETP)") (class "Default")
      (node (ref "C24") (pin "2") (pinfunction "2_2") (pintype "passive"))
      (node (ref "U7") (pin "8") (pinfunction "SETP_8") (pintype "passive"))
    )
    (net (code "78") (name "Net-(USB1-CC1)") (class "Default")
      (node (ref "R8") (pin "1") (pinfunction "1_1") (pintype "passive"))
      (node (ref "USB1") (pin "A5") (pinfunction "CC1_A5") (pintype "passive"))
    )
    (net (code "79") (name "Net-(USB1-CC2)") (class "Default")
      (node (ref "R7") (pin "1") (pinfunction "1_1") (pintype "passive"))
      (node (ref "USB1") (pin "B5") (pinfunction "CC2_B5") (pintype "passive"))
    )
    (net (code "80") (name "VBUS") (class "Default")
      (node (ref "F1") (pin "1") (pinfunction "1_1") (pintype "passive"))
      (node (ref "USB1") (pin "A4B9") (pinfunction "VBUS_A4B9") (pintype "passive"))
    )
    (net (code "81") (name "unconnected-(FPC1-Pad11)") (class "Default")
      (node (ref "FPC1") (pin "11") (pinfunction "11_11") (pintype "passive"))
    )
    (net (code "82") (name "unconnected-(FPC1-Pad22)") (class "Default")
      (node (ref "FPC1") (pin "22") (pinfunction "22_22") (pintype "passive"))
    )
    (net (code "83") (name "unconnected-(FPC1-Pad25)") (class "Default")
      (node (ref "FPC1") (pin "25") (pinfunction "25_25") (pintype "passive"))
    )
    (net (code "84") (name "unconnected-(FPC1-Pad26)") (class "Default")
      (node (ref "FPC1") (pin "26") (pinfunction "26_26") (pintype "passive"))
    )
    (net (code "85") (name "unconnected-(OLED1-C1N-Pad4)") (class "Default")
      (node (ref "OLED1") (pin "4") (pinfunction "C1N_4") (pintype "passive"))
    )
    (net (code "86") (name "unconnected-(OLED1-C1P-Pad3)") (class "Default")
      (node (ref "OLED1") (pin "3") (pinfunction "C1P_3") (pintype "passive"))
    )
    (net (code "87") (name "unconnected-(OLED1-C2N-Pad2)") (class "Default")
      (node (ref "OLED1") (pin "2") (pinfunction "C2N_2") (pintype "passive"))
    )
    (net (code "88") (name "unconnected-(OLED1-C2P-Pad1)") (class "Default")
      (node (ref "OLED1") (pin "1") (pinfunction "C2P_1") (pintype "passive"))
    )
    (net (code "89") (name "unconnected-(OLED1-RES#-Pad9)") (class "Default")
      (node (ref "OLED1") (pin "9") (pinfunction "RES#_9") (pintype "passive"))
    )
    (net (code "90") (name "unconnected-(OLED1-SCL-Pad10)") (class "Default")
      (node (ref "OLED1") (pin "10") (pinfunction "SCL_10") (pintype "passive"))
    )
    (net (code "91") (name "unconnected-(OLED1-SDA-Pad11)") (class "Default")
      (node (ref "OLED1") (pin "11") (pinfunction "SDA_11") (pintype "passive"))
    )
    (net (code "92") (name "unconnected-(OLED1-VBREF-Pad6)") (class "Default")
      (node (ref "OLED1") (pin "6") (pinfunction "VBREF_6") (pintype "passive"))
    )
    (net (code "93") (name "unconnected-(U2-CTS#-Pad9)") (class "Default")
      (node (ref "U2") (pin "9") (pinfunction "CTS#_9") (pintype "passive"))
    )
    (net (code "94") (name "unconnected-(U2-DCD#-Pad12)") (class "Default")
      (node (ref "U2") (pin "12") (pinfunction "DCD#_12") (pintype "passive"))
    )
    (net (code "95") (name "unconnected-(U2-DSR#-Pad10)") (class "Default")
      (node (ref "U2") (pin "10") (pinfunction "DSR#_10") (pintype "passive"))
    )
    (net (code "96") (name "unconnected-(U2-R232-Pad15)") (class "Default")
      (node (ref "U2") (pin "15") (pinfunction "R232_15") (pintype "passive"))
    )
    (net (code "97") (name "unconnected-(U2-RI#-Pad11)") (class "Default")
      (node (ref "U2") (pin "11") (pinfunction "RI#_11") (pintype "passive"))
    )
    (net (code "98") (name "unconnected-(U4-CAP1-Pad48)") (class "Default")
      (node (ref "U4") (pin "48") (pinfunction "CAP1_48") (pintype "passive"))
    )
    (net (code "99") (name "unconnected-(U4-CAP2-Pad47)") (class "Default")
      (node (ref "U4") (pin "47") (pinfunction "CAP2_47") (pintype "passive"))
    )
    (net (code "100") (name "unconnected-(U4-XTAL_N-Pad44)") (class "Default")
      (node (ref "U4") (pin "44") (pinfunction "XTAL_N_44") (pintype "passive"))
    )
    (net (code "101") (name "unconnected-(U4-XTAL_P-Pad45)") (class "Default")
      (node (ref "U4") (pin "45") (pinfunction "XTAL_P_45") (pintype "passive"))
    )
    (net (code "102") (name "unconnected-(U6-AUX_CL-Pad7)") (class "Default")
      (node (ref "U6") (pin "7") (pinfunction "AUX_CL_7") (pintype "passive"))
    )
    (net (code "103") (name "unconnected-(U6-AUX_DA-Pad6)") (class "Default")
      (node (ref "U6") (pin "6") (pinfunction "AUX_DA_6") (pintype "passive"))
    )
    (net (code "104") (name "unconnected-(U6-NC-Pad2)") (class "Default")
      (node (ref "U6") (pin "2") (pinfunction "NC_2") (pintype "passive"))
    )
    (net (code "105") (name "unconnected-(U6-NC-Pad3)") (class "Default")
      (node (ref "U6") (pin "3") (pinfunction "NC_3") (pintype "passive"))
    )
    (net (code "106") (name "unconnected-(U6-NC-Pad4)") (class "Default")
      (node (ref "U6") (pin "4") (pinfunction "NC_4") (pintype "passive"))
    )
    (net (code "107") (name "unconnected-(U6-NC-Pad5)") (class "Default")
      (node (ref "U6") (pin "5") (pinfunction "NC_5") (pintype "passive"))
    )
    (net (code "108") (name "unconnected-(U6-NC-Pad14)") (class "Default")
      (node (ref "U6") (pin "14") (pinfunction "NC_14") (pintype "passive"))
    )
    (net (code "109") (name "unconnected-(U6-NC-Pad15)") (class "Default")
      (node (ref "U6") (pin "15") (pinfunction "NC_15") (pintype "passive"))
    )
    (net (code "110") (name "unconnected-(U6-NC-Pad16)") (class "Default")
      (node (ref "U6") (pin "16") (pinfunction "NC_16") (pintype "passive"))
    )
    (net (code "111") (name "unconnected-(U6-NC-Pad17)") (class "Default")
      (node (ref "U6") (pin "17") (pinfunction "NC_17") (pintype "passive"))
    )
    (net (code "112") (name "unconnected-(U6-RESV-Pad19)") (class "Default")
      (node (ref "U6") (pin "19") (pinfunction "RESV_19") (pintype "passive"))
    )
    (net (code "113") (name "unconnected-(U6-RESV-Pad21)") (class "Default")
      (node (ref "U6") (pin "21") (pinfunction "RESV_21") (pintype "passive"))
    )
    (net (code "114") (name "unconnected-(U6-RESV-Pad22)") (class "Default")
      (node (ref "U6") (pin "22") (pinfunction "RESV_22") (pintype "passive"))
    )
    (net (code "115") (name "unconnected-(U7-DRDY-Pad15)") (class "Default")
      (node (ref "U7") (pin "15") (pinfunction "DRDY_15") (pintype "passive"))
    )
    (net (code "116") (name "unconnected-(U7-I2C{slash}SPI-Pad6)") (class "Default")
      (node (ref "U7") (pin "6") (pinfunction "I2C/SPI_6") (pintype "passive"))
    )
    (net (code "117") (name "unconnected-(U7-NC-Pad3)") (class "Default")
      (node (ref "U7") (pin "3") (pinfunction "NC_3") (pintype "passive"))
    )
    (net (code "118") (name "unconnected-(U7-NC-Pad5)") (class "Default")
      (node (ref "U7") (pin "5") (pinfunction "NC_5") (pintype "passive"))
    )
    (net (code "119") (name "unconnected-(U7-NC-Pad7)") (class "Default")
      (node (ref "U7") (pin "7") (pinfunction "NC_7") (pintype "passive"))
    )
    (net (code "120") (name "unconnected-(U7-NC-Pad14)") (class "Default")
      (node (ref "U7") (pin "14") (pinfunction "NC_14") (pintype "passive"))
    )
    (net (code "121") (name "unconnected-(U7-S1-Pad4)") (class "Default")
      (node (ref "U7") (pin "4") (pinfunction "S1_4") (pintype "passive"))
    )
    (net (code "122") (name "unconnected-(U8-SDO-Pad6)") (class "Default")
      (node (ref "U8") (pin "6") (pinfunction "SDO_6") (pintype "passive"))
    )
    (net (code "123") (name "unconnected-(USB1-GND-PadB1A12)") (class "Default")
      (node (ref "USB1") (pin "B1A12") (pinfunction "GND_B1A12") (pintype "passive"))
    )
    (net (code "124") (name "unconnected-(USB1-SBU1-PadA8)") (class "Default")
      (node (ref "USB1") (pin "A8") (pinfunction "SBU1_A8") (pintype "passive"))
    )
    (net (code "125") (name "unconnected-(USB1-SBU2-PadB8)") (class "Default")
      (node (ref "USB1") (pin "B8") (pinfunction "SBU2_B8") (pintype "passive"))
    )
    (net (code "126") (name "unconnected-(USB1-VBUS-PadB4A9)") (class "Default")
      (node (ref "USB1") (pin "B4A9") (pinfunction "VBUS_B4A9") (pintype "passive"))
    )
  )
)
